# Large_Relay.net
KiCad netlist of a schematic drawn in Altium Designer
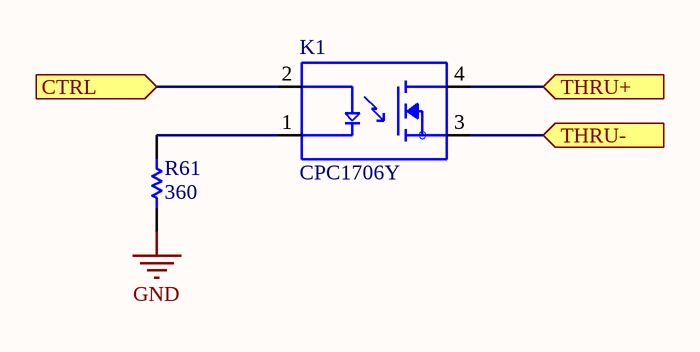
[diagram p0: Large_Relay.SchDoc]

(export (version "E")
  (design (tool "Eeschema 10.0.6"))
  (components
    (comp (ref "K1")
      (value "CPC1706Y")
      (footprint "RELAY_CPC1706Y")
      (description "Solid State SPST-NO _1 Form A_ 8-SIP, 4 Leads")
      (fields (field (name "MF") "IXYS Integrated"))
      (libsource (lib "Arturo_Approved") (part "CPC1706Y"))
    )
    (comp (ref "R61")
      (value "360")
      (footprint "0402_Res")
      (description "7.5K 1% 1/4W")
      (libsource (lib "Arturo_Approved") (part "ERJ-PB6D7501V"))
    )
  )
  (nets
    (net (code "1") (name "/CTRL") (class "Default")
      (node (ref "K1") (pin "2") (pinfunction "2_2") (pintype "passive"))
    )
    (net (code "2") (name "/THRU+") (class "Default")
      (node (ref "K1") (pin "4") (pinfunction "4_4") (pintype "passive"))
    )
    (net (code "3") (name "/THRU-") (class "Default")
      (node (ref "K1") (pin "3") (pinfunction "3_3") (pintype "passive"))
    )
    (net (code "4") (name "GND") (class "Default")
      (node (ref "R61") (pin "1") (pinfunction "1_1") (pintype "passive"))
    )
    (net (code "5") (name "Net-(K1-Pad1)") (class "Default")
      (node (ref "K1") (pin "1") (pinfunction "1_1") (pintype "passive"))
      (node (ref "R61") (pin "2") (pinfunction "2_2") (pintype "passive"))
    )
  )
)
